# decade_resistance.net
KiCad netlist of a schematic drawn in EAGLE
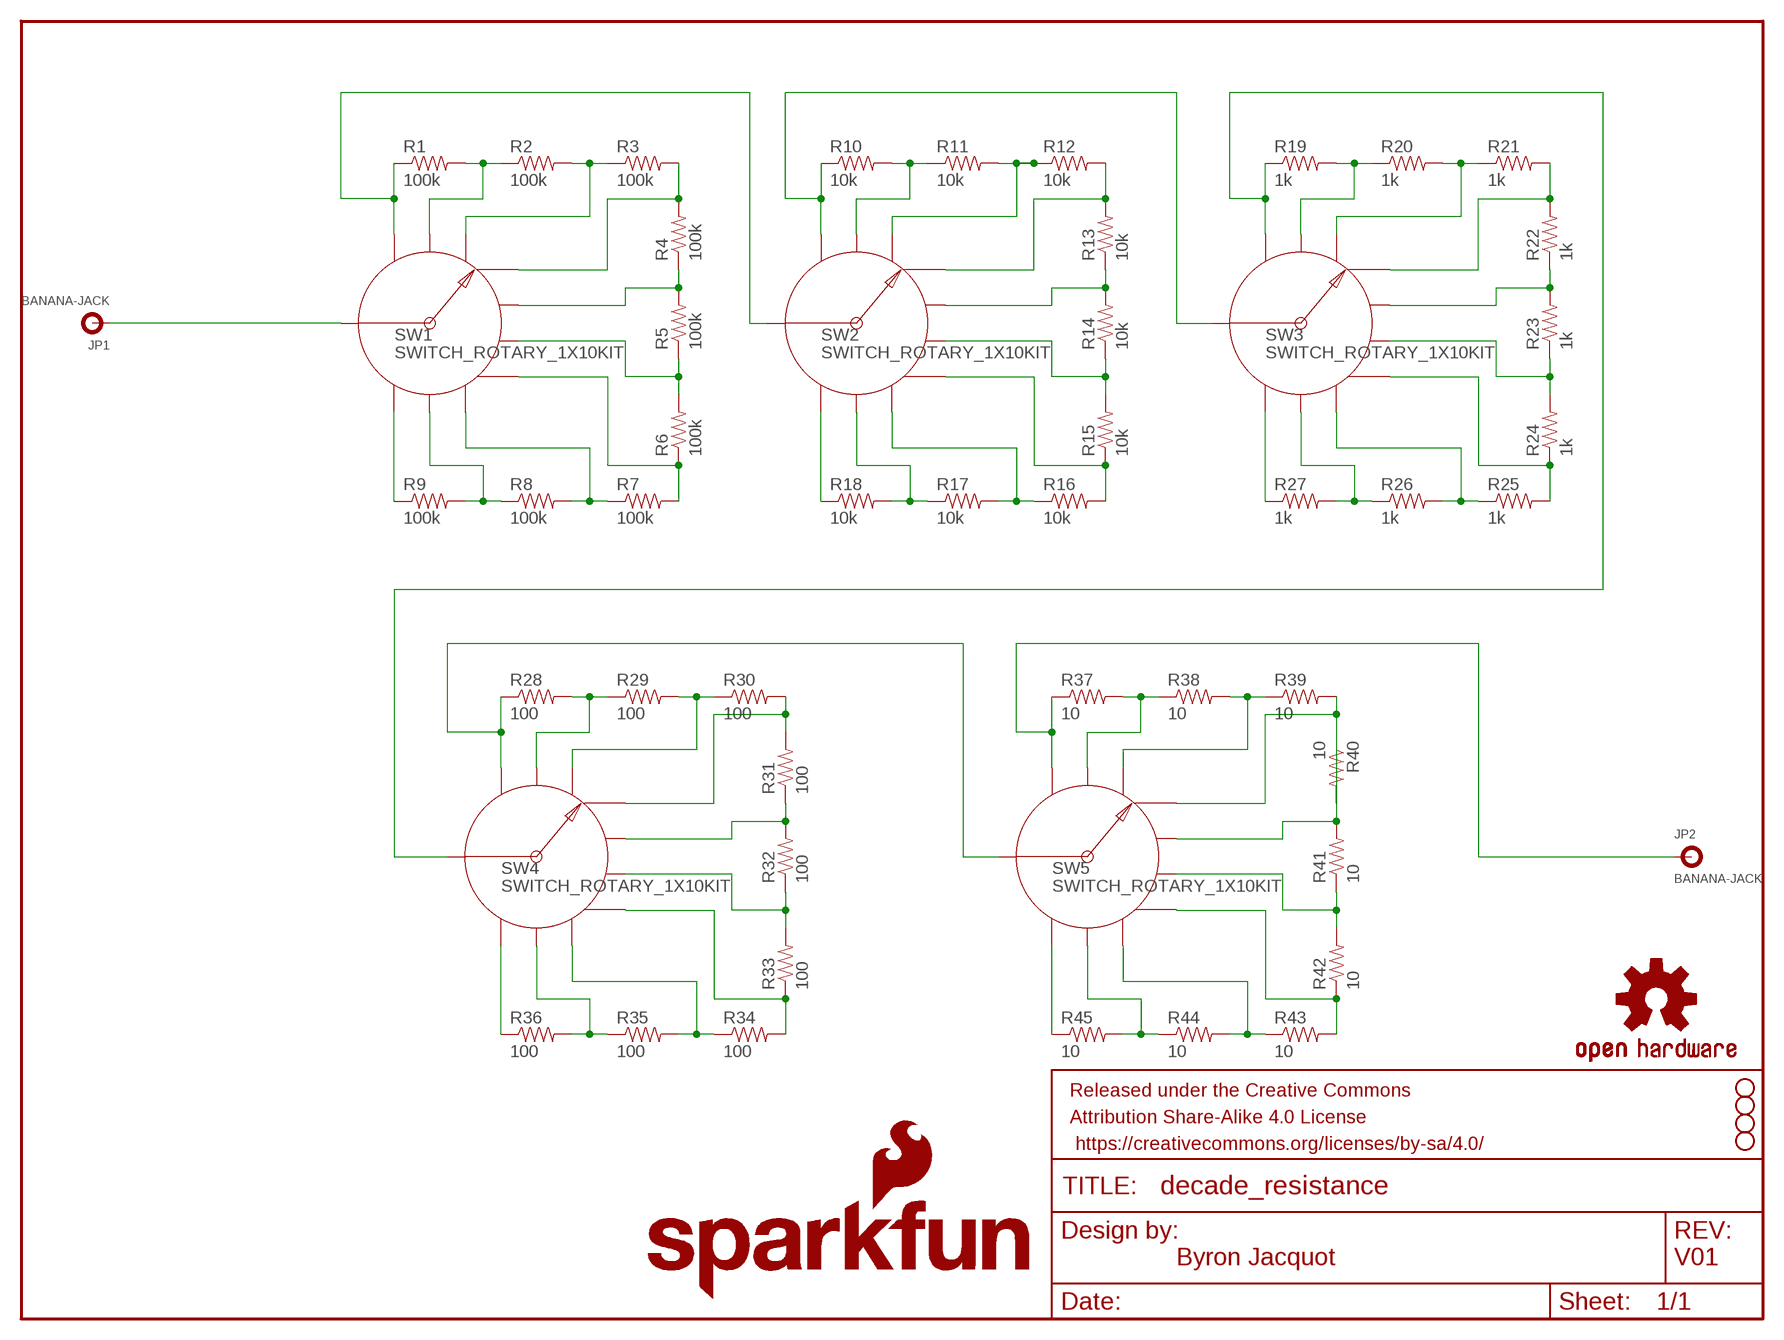
[diagram p0: schematic, sheet 1]

(export (version "E")
  (design (tool "Eeschema 10.0.6"))
  (components
    (comp (ref "FRAME1")
      (value "FRAME-LETTER")
      (footprint "eagle-import:CREATIVE_COMMONS")
      (libsource (lib "eagle-import") (part "FRAME-LETTER"))
    )
    (comp (ref "JP1")
      (value "BANANA-JACK")
      (footprint "eagle-import:BANANA-JACK")
      (libsource (lib "eagle-import") (part "BANANA-JACK"))
    )
    (comp (ref "JP2")
      (value "BANANA-JACK")
      (footprint "eagle-import:BANANA-JACK")
      (libsource (lib "eagle-import") (part "BANANA-JACK"))
    )
    (comp (ref "LOGO1")
      (value "OSHW-LOGOL")
      (footprint "eagle-import:OSHW-LOGO-L")
      (libsource (lib "eagle-import") (part "OSHW-LOGOL"))
    )
    (comp (ref "LOGO2")
      (value "SFE_LOGO_NAME_FLAME.2_INCH")
      (footprint "eagle-import:SFE_LOGO_NAME_FLAME_.2")
      (libsource (lib "eagle-import") (part "SFE_LOGO_NAME_FLAME.2_INCH"))
    )
    (comp (ref "LOGO3")
      (value "SFE_LOGO_NAME_FLAME.5_INCH")
      (footprint "eagle-import:SFE_LOGO_NAME_FLAME_.5")
      (libsource (lib "eagle-import") (part "SFE_LOGO_NAME_FLAME.5_INCH"))
    )
    (comp (ref "LOGO4")
      (value "OSHW-LOGOL")
      (footprint "eagle-import:OSHW-LOGO-L")
      (libsource (lib "eagle-import") (part "OSHW-LOGOL"))
    )
    (comp (ref "R1")
      (value "100k")
      (footprint "eagle-import:AXIAL-0.1EZ")
      (libsource (lib "eagle-import") (part "100KOHM-1/4W-5%(PTH)VERT-KIT"))
    )
    (comp (ref "R2")
      (value "100k")
      (footprint "eagle-import:AXIAL-0.1EZ")
      (libsource (lib "eagle-import") (part "100KOHM-1/4W-5%(PTH)VERT-KIT"))
    )
    (comp (ref "R3")
      (value "100k")
      (footprint "eagle-import:AXIAL-0.1EZ")
      (libsource (lib "eagle-import") (part "100KOHM-1/4W-5%(PTH)VERT-KIT"))
    )
    (comp (ref "R4")
      (value "100k")
      (footprint "eagle-import:AXIAL-0.1EZ")
      (libsource (lib "eagle-import") (part "100KOHM-1/4W-5%(PTH)VERT-KIT"))
    )
    (comp (ref "R5")
      (value "100k")
      (footprint "eagle-import:AXIAL-0.1EZ")
      (libsource (lib "eagle-import") (part "100KOHM-1/4W-5%(PTH)VERT-KIT"))
    )
    (comp (ref "R6")
      (value "100k")
      (footprint "eagle-import:AXIAL-0.1EZ")
      (libsource (lib "eagle-import") (part "100KOHM-1/4W-5%(PTH)VERT-KIT"))
    )
    (comp (ref "R7")
      (value "100k")
      (footprint "eagle-import:AXIAL-0.1EZ")
      (libsource (lib "eagle-import") (part "100KOHM-1/4W-5%(PTH)VERT-KIT"))
    )
    (comp (ref "R8")
      (value "100k")
      (footprint "eagle-import:AXIAL-0.1EZ")
      (libsource (lib "eagle-import") (part "100KOHM-1/4W-5%(PTH)VERT-KIT"))
    )
    (comp (ref "R9")
      (value "100k")
      (footprint "eagle-import:AXIAL-0.1EZ")
      (libsource (lib "eagle-import") (part "100KOHM-1/4W-5%(PTH)VERT-KIT"))
    )
    (comp (ref "R10")
      (value "10k")
      (footprint "eagle-import:AXIAL-0.1EZ")
      (libsource (lib "eagle-import") (part "10KOHM-1/4W5%(PTH)VERT-KIT"))
    )
    (comp (ref "R11")
      (value "10k")
      (footprint "eagle-import:AXIAL-0.1EZ")
      (libsource (lib "eagle-import") (part "10KOHM-1/4W5%(PTH)VERT-KIT"))
    )
    (comp (ref "R12")
      (value "10k")
      (footprint "eagle-import:AXIAL-0.1EZ")
      (libsource (lib "eagle-import") (part "10KOHM-1/4W5%(PTH)VERT-KIT"))
    )
    (comp (ref "R13")
      (value "10k")
      (footprint "eagle-import:AXIAL-0.1EZ")
      (libsource (lib "eagle-import") (part "10KOHM-1/4W5%(PTH)VERT-KIT"))
    )
    (comp (ref "R14")
      (value "10k")
      (footprint "eagle-import:AXIAL-0.1EZ")
      (libsource (lib "eagle-import") (part "10KOHM-1/4W5%(PTH)VERT-KIT"))
    )
    (comp (ref "R15")
      (value "10k")
      (footprint "eagle-import:AXIAL-0.1EZ")
      (libsource (lib "eagle-import") (part "10KOHM-1/4W5%(PTH)VERT-KIT"))
    )
    (comp (ref "R16")
      (value "10k")
      (footprint "eagle-import:AXIAL-0.1EZ")
      (libsource (lib "eagle-import") (part "10KOHM-1/4W5%(PTH)VERT-KIT"))
    )
    (comp (ref "R17")
      (value "10k")
      (footprint "eagle-import:AXIAL-0.1EZ")
      (libsource (lib "eagle-import") (part "10KOHM-1/4W5%(PTH)VERT-KIT"))
    )
    (comp (ref "R18")
      (value "10k")
      (footprint "eagle-import:AXIAL-0.1EZ")
      (libsource (lib "eagle-import") (part "10KOHM-1/4W5%(PTH)VERT-KIT"))
    )
    (comp (ref "R19")
      (value "1k")
      (footprint "eagle-import:AXIAL-0.1EZ")
      (libsource (lib "eagle-import") (part "1KOHM1/4W5%(PTH)VERT-KIT"))
    )
    (comp (ref "R20")
      (value "1k")
      (footprint "eagle-import:AXIAL-0.1EZ")
      (libsource (lib "eagle-import") (part "1KOHM1/4W5%(PTH)VERT-KIT"))
    )
    (comp (ref "R21")
      (value "1k")
      (footprint "eagle-import:AXIAL-0.1EZ")
      (libsource (lib "eagle-import") (part "1KOHM1/4W5%(PTH)VERT-KIT"))
    )
    (comp (ref "R22")
      (value "1k")
      (footprint "eagle-import:AXIAL-0.1EZ")
      (libsource (lib "eagle-import") (part "1KOHM1/4W5%(PTH)VERT-KIT"))
    )
    (comp (ref "R23")
      (value "1k")
      (footprint "eagle-import:AXIAL-0.1EZ")
      (libsource (lib "eagle-import") (part "1KOHM1/4W5%(PTH)VERT-KIT"))
    )
    (comp (ref "R24")
      (value "1k")
      (footprint "eagle-import:AXIAL-0.1EZ")
      (libsource (lib "eagle-import") (part "1KOHM1/4W5%(PTH)VERT-KIT"))
    )
    (comp (ref "R25")
      (value "1k")
      (footprint "eagle-import:AXIAL-0.1EZ")
      (libsource (lib "eagle-import") (part "1KOHM1/4W5%(PTH)VERT-KIT"))
    )
    (comp (ref "R26")
      (value "1k")
      (footprint "eagle-import:AXIAL-0.1EZ")
      (libsource (lib "eagle-import") (part "1KOHM1/4W5%(PTH)VERT-KIT"))
    )
    (comp (ref "R27")
      (value "1k")
      (footprint "eagle-import:AXIAL-0.1EZ")
      (libsource (lib "eagle-import") (part "1KOHM1/4W5%(PTH)VERT-KIT"))
    )
    (comp (ref "R28")
      (value "100")
      (footprint "eagle-import:AXIAL-0.1EZ")
      (libsource (lib "eagle-import") (part "100OHM1/4W5%(PTH)VERT-KIT"))
    )
    (comp (ref "R29")
      (value "100")
      (footprint "eagle-import:AXIAL-0.1EZ")
      (libsource (lib "eagle-import") (part "100OHM1/4W5%(PTH)VERT-KIT"))
    )
    (comp (ref "R30")
      (value "100")
      (footprint "eagle-import:AXIAL-0.1EZ")
      (libsource (lib "eagle-import") (part "100OHM1/4W5%(PTH)VERT-KIT"))
    )
    (comp (ref "R31")
      (value "100")
      (footprint "eagle-import:AXIAL-0.1EZ")
      (libsource (lib "eagle-import") (part "100OHM1/4W5%(PTH)VERT-KIT"))
    )
    (comp (ref "R32")
      (value "100")
      (footprint "eagle-import:AXIAL-0.1EZ")
      (libsource (lib "eagle-import") (part "100OHM1/4W5%(PTH)VERT-KIT"))
    )
    (comp (ref "R33")
      (value "100")
      (footprint "eagle-import:AXIAL-0.1EZ")
      (libsource (lib "eagle-import") (part "100OHM1/4W5%(PTH)VERT-KIT"))
    )
    (comp (ref "R34")
      (value "100")
      (footprint "eagle-import:AXIAL-0.1EZ")
      (libsource (lib "eagle-import") (part "100OHM1/4W5%(PTH)VERT-KIT"))
    )
    (comp (ref "R35")
      (value "100")
      (footprint "eagle-import:AXIAL-0.1EZ")
      (libsource (lib "eagle-import") (part "100OHM1/4W5%(PTH)VERT-KIT"))
    )
    (comp (ref "R36")
      (value "100")
      (footprint "eagle-import:AXIAL-0.1EZ")
      (libsource (lib "eagle-import") (part "100OHM1/4W5%(PTH)VERT-KIT"))
    )
    (comp (ref "R37")
      (value "10")
      (footprint "eagle-import:AXIAL-0.1EZ")
      (libsource (lib "eagle-import") (part "10OHM-1/4W-5%(PTH)VERT-KIT"))
    )
    (comp (ref "R38")
      (value "10")
      (footprint "eagle-import:AXIAL-0.1EZ")
      (libsource (lib "eagle-import") (part "10OHM-1/4W-5%(PTH)VERT-KIT"))
    )
    (comp (ref "R39")
      (value "10")
      (footprint "eagle-import:AXIAL-0.1EZ")
      (libsource (lib "eagle-import") (part "10OHM-1/4W-5%(PTH)VERT-KIT"))
    )
    (comp (ref "R40")
      (value "10")
      (footprint "eagle-import:AXIAL-0.1EZ")
      (libsource (lib "eagle-import") (part "10OHM-1/4W-5%(PTH)VERT-KIT"))
    )
    (comp (ref "R41")
      (value "10")
      (footprint "eagle-import:AXIAL-0.1EZ")
      (libsource (lib "eagle-import") (part "10OHM-1/4W-5%(PTH)VERT-KIT"))
    )
    (comp (ref "R42")
      (value "10")
      (footprint "eagle-import:AXIAL-0.1EZ")
      (libsource (lib "eagle-import") (part "10OHM-1/4W-5%(PTH)VERT-KIT"))
    )
    (comp (ref "R43")
      (value "10")
      (footprint "eagle-import:AXIAL-0.1EZ")
      (libsource (lib "eagle-import") (part "10OHM-1/4W-5%(PTH)VERT-KIT"))
    )
    (comp (ref "R44")
      (value "10")
      (footprint "eagle-import:AXIAL-0.1EZ")
      (libsource (lib "eagle-import") (part "10OHM-1/4W-5%(PTH)VERT-KIT"))
    )
    (comp (ref "R45")
      (value "10")
      (footprint "eagle-import:AXIAL-0.1EZ")
      (libsource (lib "eagle-import") (part "10OHM-1/4W-5%(PTH)VERT-KIT"))
    )
    (comp (ref "STANDOFF1")
      (value "STAND-OFF")
      (footprint "eagle-import:STAND-OFF")
      (libsource (lib "eagle-import") (part "STAND-OFF"))
    )
    (comp (ref "STANDOFF2")
      (value "STAND-OFF")
      (footprint "eagle-import:STAND-OFF")
      (libsource (lib "eagle-import") (part "STAND-OFF"))
    )
    (comp (ref "STANDOFF3")
      (value "STAND-OFF")
      (footprint "eagle-import:STAND-OFF")
      (libsource (lib "eagle-import") (part "STAND-OFF"))
    )
    (comp (ref "STANDOFF4")
      (value "STAND-OFF")
      (footprint "eagle-import:STAND-OFF")
      (libsource (lib "eagle-import") (part "STAND-OFF"))
    )
    (comp (ref "SW1")
      (value "SWITCH_ROTARY_1X10KIT")
      (footprint "eagle-import:ROTARY_SWITCH_1X10_KIT")
      (libsource (lib "eagle-import") (part "SWITCH_ROTARY_1X10KIT"))
    )
    (comp (ref "SW2")
      (value "SWITCH_ROTARY_1X10KIT")
      (footprint "eagle-import:ROTARY_SWITCH_1X10_KIT")
      (libsource (lib "eagle-import") (part "SWITCH_ROTARY_1X10KIT"))
    )
    (comp (ref "SW3")
      (value "SWITCH_ROTARY_1X10KIT")
      (footprint "eagle-import:ROTARY_SWITCH_1X10_KIT")
      (libsource (lib "eagle-import") (part "SWITCH_ROTARY_1X10KIT"))
    )
    (comp (ref "SW4")
      (value "SWITCH_ROTARY_1X10KIT")
      (footprint "eagle-import:ROTARY_SWITCH_1X10_KIT")
      (libsource (lib "eagle-import") (part "SWITCH_ROTARY_1X10KIT"))
    )
    (comp (ref "SW5")
      (value "SWITCH_ROTARY_1X10KIT")
      (footprint "eagle-import:ROTARY_SWITCH_1X10_KIT")
      (libsource (lib "eagle-import") (part "SWITCH_ROTARY_1X10KIT"))
    )
  )
  (nets
    (net (code "1") (name "Net-(JP1-PadP$1)") (class "Default")
      (node (ref "JP1") (pin "P$1") (pinfunction "P$1_P$1") (pintype "bidirectional"))
      (node (ref "SW1") (pin "COMMON") (pinfunction "COMMON_COMMON") (pintype "bidirectional"))
    )
    (net (code "2") (name "Net-(R1-1)") (class "Default")
      (node (ref "R1") (pin "P$1") (pinfunction "1_P$1") (pintype "passive"))
      (node (ref "SW1") (pin "1") (pinfunction "1_1") (pintype "bidirectional"))
      (node (ref "SW2") (pin "COMMON") (pinfunction "COMMON_COMMON") (pintype "bidirectional"))
    )
    (net (code "3") (name "Net-(R1-2)") (class "Default")
      (node (ref "R1") (pin "P$2") (pinfunction "2_P$2") (pintype "passive"))
      (node (ref "R2") (pin "P$1") (pinfunction "1_P$1") (pintype "passive"))
      (node (ref "SW1") (pin "2") (pinfunction "2_2") (pintype "bidirectional"))
    )
    (net (code "4") (name "Net-(R2-2)") (class "Default")
      (node (ref "R2") (pin "P$2") (pinfunction "2_P$2") (pintype "passive"))
      (node (ref "R3") (pin "P$1") (pinfunction "1_P$1") (pintype "passive"))
      (node (ref "SW1") (pin "3") (pinfunction "3_3") (pintype "bidirectional"))
    )
    (net (code "5") (name "Net-(R3-2)") (class "Default")
      (node (ref "R3") (pin "P$2") (pinfunction "2_P$2") (pintype "passive"))
      (node (ref "R4") (pin "P$2") (pinfunction "2_P$2") (pintype "passive"))
      (node (ref "SW1") (pin "4") (pinfunction "4_4") (pintype "bidirectional"))
    )
    (net (code "6") (name "Net-(R4-1)") (class "Default")
      (node (ref "R4") (pin "P$1") (pinfunction "1_P$1") (pintype "passive"))
      (node (ref "R5") (pin "P$2") (pinfunction "2_P$2") (pintype "passive"))
      (node (ref "SW1") (pin "5") (pinfunction "5_5") (pintype "bidirectional"))
    )
    (net (code "7") (name "Net-(R5-1)") (class "Default")
      (node (ref "R5") (pin "P$1") (pinfunction "1_P$1") (pintype "passive"))
      (node (ref "R6") (pin "P$2") (pinfunction "2_P$2") (pintype "passive"))
      (node (ref "SW1") (pin "6") (pinfunction "6_6") (pintype "bidirectional"))
    )
    (net (code "8") (name "Net-(R6-1)") (class "Default")
      (node (ref "R6") (pin "P$1") (pinfunction "1_P$1") (pintype "passive"))
      (node (ref "R7") (pin "P$2") (pinfunction "2_P$2") (pintype "passive"))
      (node (ref "SW1") (pin "7") (pinfunction "7_7") (pintype "bidirectional"))
    )
    (net (code "9") (name "Net-(R7-1)") (class "Default")
      (node (ref "R7") (pin "P$1") (pinfunction "1_P$1") (pintype "passive"))
      (node (ref "R8") (pin "P$2") (pinfunction "2_P$2") (pintype "passive"))
      (node (ref "SW1") (pin "8") (pinfunction "8_8") (pintype "bidirectional"))
    )
    (net (code "10") (name "Net-(R8-1)") (class "Default")
      (node (ref "R8") (pin "P$1") (pinfunction "1_P$1") (pintype "passive"))
      (node (ref "R9") (pin "P$2") (pinfunction "2_P$2") (pintype "passive"))
      (node (ref "SW1") (pin "9") (pinfunction "9_9") (pintype "bidirectional"))
    )
    (net (code "11") (name "Net-(R9-1)") (class "Default")
      (node (ref "R9") (pin "P$1") (pinfunction "1_P$1") (pintype "passive"))
      (node (ref "SW1") (pin "10") (pinfunction "10_10") (pintype "bidirectional"))
    )
    (net (code "12") (name "Net-(R10-1)") (class "Default")
      (node (ref "R10") (pin "P$1") (pinfunction "1_P$1") (pintype "passive"))
      (node (ref "SW2") (pin "1") (pinfunction "1_1") (pintype "bidirectional"))
      (node (ref "SW3") (pin "COMMON") (pinfunction "COMMON_COMMON") (pintype "bidirectional"))
    )
    (net (code "13") (name "Net-(R10-2)") (class "Default")
      (node (ref "R10") (pin "P$2") (pinfunction "2_P$2") (pintype "passive"))
      (node (ref "R11") (pin "P$1") (pinfunction "1_P$1") (pintype "passive"))
      (node (ref "SW2") (pin "2") (pinfunction "2_2") (pintype "bidirectional"))
    )
    (net (code "14") (name "Net-(R11-2)") (class "Default")
      (node (ref "R11") (pin "P$2") (pinfunction "2_P$2") (pintype "passive"))
      (node (ref "R12") (pin "P$1") (pinfunction "1_P$1") (pintype "passive"))
      (node (ref "SW2") (pin "3") (pinfunction "3_3") (pintype "bidirectional"))
    )
    (net (code "15") (name "Net-(R12-2)") (class "Default")
      (node (ref "R12") (pin "P$2") (pinfunction "2_P$2") (pintype "passive"))
      (node (ref "R13") (pin "P$2") (pinfunction "2_P$2") (pintype "passive"))
      (node (ref "SW2") (pin "4") (pinfunction "4_4") (pintype "bidirectional"))
    )
    (net (code "16") (name "Net-(R13-1)") (class "Default")
      (node (ref "R13") (pin "P$1") (pinfunction "1_P$1") (pintype "passive"))
      (node (ref "R14") (pin "P$2") (pinfunction "2_P$2") (pintype "passive"))
      (node (ref "SW2") (pin "5") (pinfunction "5_5") (pintype "bidirectional"))
    )
    (net (code "17") (name "Net-(R14-1)") (class "Default")
      (node (ref "R14") (pin "P$1") (pinfunction "1_P$1") (pintype "passive"))
      (node (ref "R15") (pin "P$2") (pinfunction "2_P$2") (pintype "passive"))
      (node (ref "SW2") (pin "6") (pinfunction "6_6") (pintype "bidirectional"))
    )
    (net (code "18") (name "Net-(R15-1)") (class "Default")
      (node (ref "R15") (pin "P$1") (pinfunction "1_P$1") (pintype "passive"))
      (node (ref "R16") (pin "P$2") (pinfunction "2_P$2") (pintype "passive"))
      (node (ref "SW2") (pin "7") (pinfunction "7_7") (pintype "bidirectional"))
    )
    (net (code "19") (name "Net-(R16-1)") (class "Default")
      (node (ref "R16") (pin "P$1") (pinfunction "1_P$1") (pintype "passive"))
      (node (ref "R17") (pin "P$2") (pinfunction "2_P$2") (pintype "passive"))
      (node (ref "SW2") (pin "8") (pinfunction "8_8") (pintype "bidirectional"))
    )
    (net (code "20") (name "Net-(R17-1)") (class "Default")
      (node (ref "R17") (pin "P$1") (pinfunction "1_P$1") (pintype "passive"))
      (node (ref "R18") (pin "P$2") (pinfunction "2_P$2") (pintype "passive"))
      (node (ref "SW2") (pin "9") (pinfunction "9_9") (pintype "bidirectional"))
    )
    (net (code "21") (name "Net-(R18-1)") (class "Default")
      (node (ref "R18") (pin "P$1") (pinfunction "1_P$1") (pintype "passive"))
      (node (ref "SW2") (pin "10") (pinfunction "10_10") (pintype "bidirectional"))
    )
    (net (code "22") (name "Net-(R19-1)") (class "Default")
      (node (ref "R19") (pin "P$1") (pinfunction "1_P$1") (pintype "passive"))
      (node (ref "SW3") (pin "1") (pinfunction "1_1") (pintype "bidirectional"))
      (node (ref "SW4") (pin "COMMON") (pinfunction "COMMON_COMMON") (pintype "bidirectional"))
    )
    (net (code "23") (name "Net-(R19-2)") (class "Default")
      (node (ref "R19") (pin "P$2") (pinfunction "2_P$2") (pintype "passive"))
      (node (ref "R20") (pin "P$1") (pinfunction "1_P$1") (pintype "passive"))
      (node (ref "SW3") (pin "2") (pinfunction "2_2") (pintype "bidirectional"))
    )
    (net (code "24") (name "Net-(R20-2)") (class "Default")
      (node (ref "R20") (pin "P$2") (pinfunction "2_P$2") (pintype "passive"))
      (node (ref "R21") (pin "P$1") (pinfunction "1_P$1") (pintype "passive"))
      (node (ref "SW3") (pin "3") (pinfunction "3_3") (pintype "bidirectional"))
    )
    (net (code "25") (name "Net-(R21-2)") (class "Default")
      (node (ref "R21") (pin "P$2") (pinfunction "2_P$2") (pintype "passive"))
      (node (ref "R22") (pin "P$2") (pinfunction "2_P$2") (pintype "passive"))
      (node (ref "SW3") (pin "4") (pinfunction "4_4") (pintype "bidirectional"))
    )
    (net (code "26") (name "Net-(R22-1)") (class "Default")
      (node (ref "R22") (pin "P$1") (pinfunction "1_P$1") (pintype "passive"))
      (node (ref "R23") (pin "P$2") (pinfunction "2_P$2") (pintype "passive"))
      (node (ref "SW3") (pin "5") (pinfunction "5_5") (pintype "bidirectional"))
    )
    (net (code "27") (name "Net-(R23-1)") (class "Default")
      (node (ref "R23") (pin "P$1") (pinfunction "1_P$1") (pintype "passive"))
      (node (ref "R24") (pin "P$2") (pinfunction "2_P$2") (pintype "passive"))
      (node (ref "SW3") (pin "6") (pinfunction "6_6") (pintype "bidirectional"))
    )
    (net (code "28") (name "Net-(R24-1)") (class "Default")
      (node (ref "R24") (pin "P$1") (pinfunction "1_P$1") (pintype "passive"))
      (node (ref "R25") (pin "P$2") (pinfunction "2_P$2") (pintype "passive"))
      (node (ref "SW3") (pin "7") (pinfunction "7_7") (pintype "bidirectional"))
    )
    (net (code "29") (name "Net-(R25-1)") (class "Default")
      (node (ref "R25") (pin "P$1") (pinfunction "1_P$1") (pintype "passive"))
      (node (ref "R26") (pin "P$2") (pinfunction "2_P$2") (pintype "passive"))
      (node (ref "SW3") (pin "8") (pinfunction "8_8") (pintype "bidirectional"))
    )
    (net (code "30") (name "Net-(R26-1)") (class "Default")
      (node (ref "R26") (pin "P$1") (pinfunction "1_P$1") (pintype "passive"))
      (node (ref "R27") (pin "P$2") (pinfunction "2_P$2") (pintype "passive"))
      (node (ref "SW3") (pin "9") (pinfunction "9_9") (pintype "bidirectional"))
    )
    (net (code "31") (name "Net-(R27-1)") (class "Default")
      (node (ref "R27") (pin "P$1") (pinfunction "1_P$1") (pintype "passive"))
      (node (ref "SW3") (pin "10") (pinfunction "10_10") (pintype "bidirectional"))
    )
    (net (code "32") (name "Net-(R28-1)") (class "Default")
      (node (ref "R28") (pin "P$1") (pinfunction "1_P$1") (pintype "passive"))
      (node (ref "SW4") (pin "1") (pinfunction "1_1") (pintype "bidirectional"))
      (node (ref "SW5") (pin "COMMON") (pinfunction "COMMON_COMMON") (pintype "bidirectional"))
    )
    (net (code "33") (name "Net-(R28-2)") (class "Default")
      (node (ref "R28") (pin "P$2") (pinfunction "2_P$2") (pintype "passive"))
      (node (ref "R29") (pin "P$1") (pinfunction "1_P$1") (pintype "passive"))
      (node (ref "SW4") (pin "2") (pinfunction "2_2") (pintype "bidirectional"))
    )
    (net (code "34") (name "Net-(R29-2)") (class "Default")
      (node (ref "R29") (pin "P$2") (pinfunction "2_P$2") (pintype "passive"))
      (node (ref "R30") (pin "P$1") (pinfunction "1_P$1") (pintype "passive"))
      (node (ref "SW4") (pin "3") (pinfunction "3_3") (pintype "bidirectional"))
    )
    (net (code "35") (name "Net-(R30-2)") (class "Default")
      (node (ref "R30") (pin "P$2") (pinfunction "2_P$2") (pintype "passive"))
      (node (ref "R31") (pin "P$2") (pinfunction "2_P$2") (pintype "passive"))
      (node (ref "SW4") (pin "4") (pinfunction "4_4") (pintype "bidirectional"))
    )
    (net (code "36") (name "Net-(R31-1)") (class "Default")
      (node (ref "R31") (pin "P$1") (pinfunction "1_P$1") (pintype "passive"))
      (node (ref "R32") (pin "P$2") (pinfunction "2_P$2") (pintype "passive"))
      (node (ref "SW4") (pin "5") (pinfunction "5_5") (pintype "bidirectional"))
    )
    (net (code "37") (name "Net-(R32-1)") (class "Default")
      (node (ref "R32") (pin "P$1") (pinfunction "1_P$1") (pintype "passive"))
      (node (ref "R33") (pin "P$2") (pinfunction "2_P$2") (pintype "passive"))
      (node (ref "SW4") (pin "6") (pinfunction "6_6") (pintype "bidirectional"))
    )
    (net (code "38") (name "Net-(R33-1)") (class "Default")
      (node (ref "R33") (pin "P$1") (pinfunction "1_P$1") (pintype "passive"))
      (node (ref "R34") (pin "P$2") (pinfunction "2_P$2") (pintype "passive"))
      (node (ref "SW4") (pin "7") (pinfunction "7_7") (pintype "bidirectional"))
    )
    (net (code "39") (name "Net-(R34-1)") (class "Default")
      (node (ref "R34") (pin "P$1") (pinfunction "1_P$1") (pintype "passive"))
      (node (ref "R35") (pin "P$2") (pinfunction "2_P$2") (pintype "passive"))
      (node (ref "SW4") (pin "8") (pinfunction "8_8") (pintype "bidirectional"))
    )
    (net (code "40") (name "Net-(R35-1)") (class "Default")
      (node (ref "R35") (pin "P$1") (pinfunction "1_P$1") (pintype "passive"))
      (node (ref "R36") (pin "P$2") (pinfunction "2_P$2") (pintype "passive"))
      (node (ref "SW4") (pin "9") (pinfunction "9_9") (pintype "bidirectional"))
    )
    (net (code "41") (name "Net-(R36-1)") (class "Default")
      (node (ref "R36") (pin "P$1") (pinfunction "1_P$1") (pintype "passive"))
      (node (ref "SW4") (pin "10") (pinfunction "10_10") (pintype "bidirectional"))
    )
    (net (code "42") (name "Net-(R37-1)") (class "Default")
      (node (ref "JP2") (pin "P$1") (pinfunction "P$1_P$1") (pintype "bidirectional"))
      (node (ref "R37") (pin "P$1") (pinfunction "1_P$1") (pintype "passive"))
      (node (ref "SW5") (pin "1") (pinfunction "1_1") (pintype "bidirectional"))
    )
    (net (code "43") (name "Net-(R37-2)") (class "Default")
      (node (ref "R37") (pin "P$2") (pinfunction "2_P$2") (pintype "passive"))
      (node (ref "R38") (pin "P$1") (pinfunction "1_P$1") (pintype "passive"))
      (node (ref "SW5") (pin "2") (pinfunction "2_2") (pintype "bidirectional"))
    )
    (net (code "44") (name "Net-(R38-2)") (class "Default")
      (node (ref "R38") (pin "P$2") (pinfunction "2_P$2") (pintype "passive"))
      (node (ref "R39") (pin "P$1") (pinfunction "1_P$1") (pintype "passive"))
      (node (ref "SW5") (pin "3") (pinfunction "3_3") (pintype "bidirectional"))
    )
    (net (code "45") (name "Net-(R39-2)") (class "Default")
      (node (ref "R39") (pin "P$2") (pinfunction "2_P$2") (pintype "passive"))
      (node (ref "R40") (pin "P$2") (pinfunction "2_P$2") (pintype "passive"))
      (node (ref "SW5") (pin "4") (pinfunction "4_4") (pintype "bidirectional"))
    )
    (net (code "46") (name "Net-(R40-1)") (class "Default")
      (node (ref "R40") (pin "P$1") (pinfunction "1_P$1") (pintype "passive"))
      (node (ref "R41") (pin "P$2") (pinfunction "2_P$2") (pintype "passive"))
      (node (ref "SW5") (pin "5") (pinfunction "5_5") (pintype "bidirectional"))
    )
    (net (code "47") (name "Net-(R41-1)") (class "Default")
      (node (ref "R41") (pin "P$1") (pinfunction "1_P$1") (pintype "passive"))
      (node (ref "R42") (pin "P$2") (pinfunction "2_P$2") (pintype "passive"))
      (node (ref "SW5") (pin "6") (pinfunction "6_6") (pintype "bidirectional"))
    )
    (net (code "48") (name "Net-(R42-1)") (class "Default")
      (node (ref "R42") (pin "P$1") (pinfunction "1_P$1") (pintype "passive"))
      (node (ref "R43") (pin "P$2") (pinfunction "2_P$2") (pintype "passive"))
      (node (ref "SW5") (pin "7") (pinfunction "7_7") (pintype "bidirectional"))
    )
    (net (code "49") (name "Net-(R43-1)") (class "Default")
      (node (ref "R43") (pin "P$1") (pinfunction "1_P$1") (pintype "passive"))
      (node (ref "R44") (pin "P$2") (pinfunction "2_P$2") (pintype "passive"))
      (node (ref "SW5") (pin "8") (pinfunction "8_8") (pintype "bidirectional"))
    )
    (net (code "50") (name "Net-(R44-1)") (class "Default")
      (node (ref "R44") (pin "P$1") (pinfunction "1_P$1") (pintype "passive"))
      (node (ref "R45") (pin "P$2") (pinfunction "2_P$2") (pintype "passive"))
      (node (ref "SW5") (pin "9") (pinfunction "9_9") (pintype "bidirectional"))
    )
    (net (code "51") (name "Net-(R45-1)") (class "Default")
      (node (ref "R45") (pin "P$1") (pinfunction "1_P$1") (pintype "passive"))
      (node (ref "SW5") (pin "10") (pinfunction "10_10") (pintype "bidirectional"))
    )
  )
)
